# ZLL.net
KiCad netlist of a schematic drawn in EAGLE
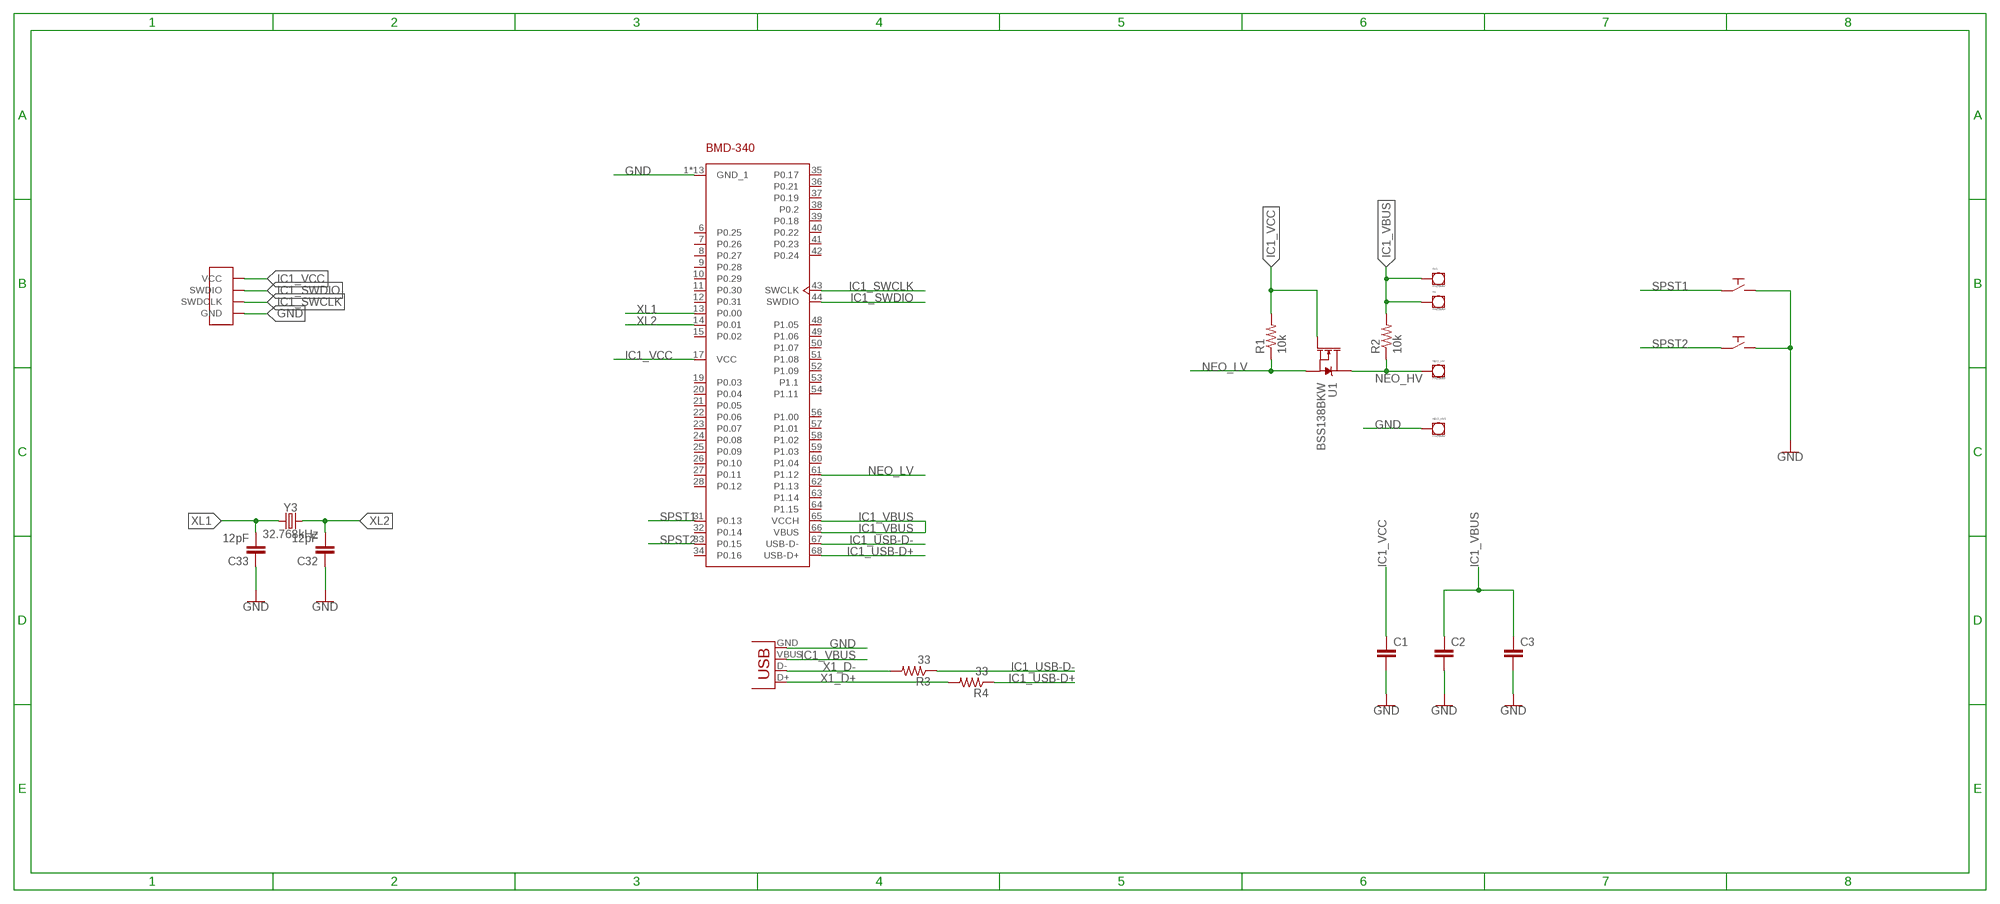
[diagram p0: schematic, sheet 1]

(export (version "E")
  (design (tool "Eeschema 10.0.6"))
  (components
    (comp (ref "5V")
      (value "PAD3MM")
      (footprint "eagle-import:PAD_3")
      (libsource (lib "eagle-import") (part "PAD3MM"))
    )
    (comp (ref "5V1")
      (value "PAD3MM")
      (footprint "eagle-import:PAD_3")
      (libsource (lib "eagle-import") (part "PAD3MM"))
    )
    (comp (ref "C1")
      (value "C-EUC0603")
      (footprint "eagle-import:C0603")
      (libsource (lib "eagle-import") (part "resistor_C-EUC0603"))
    )
    (comp (ref "C2")
      (value "C-EUC0805")
      (footprint "eagle-import:C0805")
      (libsource (lib "eagle-import") (part "resistor_C-EUC0805"))
    )
    (comp (ref "C3")
      (value "C-EUC0603")
      (footprint "eagle-import:C0603")
      (libsource (lib "eagle-import") (part "resistor_C-EUC0603"))
    )
    (comp (ref "C32")
      (value "12pF")
      (footprint "eagle-import:C0603")
      (libsource (lib "eagle-import") (part "C-EUC0603"))
    )
    (comp (ref "C33")
      (value "12pF")
      (footprint "eagle-import:C0603")
      (libsource (lib "eagle-import") (part "C-EUC0603"))
    )
    (comp (ref "IC1")
      (value "BMD-340-A-R")
      (footprint "eagle-import:BMD340AR")
      (fields (field (name "MOUSER_PART_NUMBER") "377-BMD-340-A-R"))
      (libsource (lib "eagle-import") (part "BMD-340-A-R"))
    )
    (comp (ref "NEO_HV")
      (value "PAD3MM")
      (footprint "eagle-import:PAD_3")
      (libsource (lib "eagle-import") (part "PAD3MM"))
    )
    (comp (ref "NEO_HV1")
      (value "PAD3MM")
      (footprint "eagle-import:PAD_3")
      (libsource (lib "eagle-import") (part "PAD3MM"))
    )
    (comp (ref "R1")
      (value "10k")
      (footprint "eagle-import:R0603")
      (libsource (lib "eagle-import") (part "R-US_R0603"))
    )
    (comp (ref "R2")
      (value "10k")
      (footprint "eagle-import:R0603")
      (libsource (lib "eagle-import") (part "R-US_R0603"))
    )
    (comp (ref "R3")
      (value "33")
      (footprint "eagle-import:R0603")
      (libsource (lib "eagle-import") (part "R-US_R0603"))
    )
    (comp (ref "R4")
      (value "33")
      (footprint "eagle-import:R0603")
      (libsource (lib "eagle-import") (part "R-US_R0603"))
    )
    (comp (ref "SPST1")
      (value "PTS526SK08")
      (footprint "eagle-import:PTS526SKG15SMTR2LFS")
      (libsource (lib "eagle-import") (part "PTS526SK08"))
    )
    (comp (ref "SPST2")
      (value "PTS526SK08")
      (footprint "eagle-import:PTS526SKG15SMTR2LFS")
      (libsource (lib "eagle-import") (part "PTS526SK08"))
    )
    (comp (ref "U$1")
      (value "PROG_SMD")
      (footprint "eagle-import:PROG_SMD")
      (libsource (lib "eagle-import") (part "PROG_SMD"))
    )
    (comp (ref "U1")
      (value "BSS138BKW")
      (footprint "eagle-import:SOT65P210X110-3N")
      (libsource (lib "eagle-import") (part "BSS138BKW"))
    )
    (comp (ref "X1")
      (value "USB-MICROB")
      (footprint "eagle-import:USB-MICROB")
      (libsource (lib "eagle-import") (part "USB-MICROB"))
    )
    (comp (ref "Y3")
      (value "32.768kHz")
      (footprint "eagle-import:CRYSTAL-SMD-3.2X1.5MM")
      (libsource (lib "eagle-import") (part "CRYSTAL-32.768KHZSMD-3.2X1.5"))
    )
  )
  (nets
    (net (code "1") (name "/IC1_USB-D+") (class "Default")
      (node (ref "IC1") (pin "68") (pinfunction "USB-D+_68") (pintype "bidirectional"))
      (node (ref "R4") (pin "1") (pinfunction "1_1") (pintype "passive"))
    )
    (net (code "2") (name "/IC1_USB-D-") (class "Default")
      (node (ref "IC1") (pin "67") (pinfunction "USB-D-_67") (pintype "bidirectional"))
      (node (ref "R3") (pin "1") (pinfunction "1_1") (pintype "passive"))
    )
    (net (code "3") (name "/NEO_HV") (class "Default")
      (node (ref "NEO_HV") (pin "P$1") (pinfunction "1_P$1") (pintype "passive"))
      (node (ref "R2") (pin "1") (pinfunction "1_1") (pintype "passive"))
      (node (ref "U1") (pin "3") (pinfunction "D_3") (pintype "bidirectional"))
    )
    (net (code "4") (name "/NEO_LV") (class "Default")
      (node (ref "IC1") (pin "61") (pinfunction "P1.12_61") (pintype "bidirectional"))
      (node (ref "R1") (pin "1") (pinfunction "1_1") (pintype "passive"))
      (node (ref "U1") (pin "2") (pinfunction "S_2") (pintype "bidirectional"))
    )
    (net (code "5") (name "/SPST1") (class "Default")
      (node (ref "IC1") (pin "31") (pinfunction "P0.13_31") (pintype "bidirectional"))
      (node (ref "SPST1") (pin "1") (pinfunction "P$1_1") (pintype "passive"))
      (node (ref "SPST1") (pin "2") (pinfunction "P$1_2") (pintype "passive"))
    )
    (net (code "6") (name "/SPST2") (class "Default")
      (node (ref "IC1") (pin "33") (pinfunction "P0.15_33") (pintype "bidirectional"))
      (node (ref "SPST2") (pin "1") (pinfunction "P$1_1") (pintype "passive"))
      (node (ref "SPST2") (pin "2") (pinfunction "P$1_2") (pintype "passive"))
    )
    (net (code "7") (name "/X1_D+") (class "Default")
      (node (ref "R4") (pin "2") (pinfunction "2_2") (pintype "passive"))
      (node (ref "X1") (pin "D+") (pinfunction "D+_D+") (pintype "bidirectional"))
    )
    (net (code "8") (name "/X1_D-") (class "Default")
      (node (ref "R3") (pin "2") (pinfunction "2_2") (pintype "passive"))
      (node (ref "X1") (pin "D-") (pinfunction "D-_D-") (pintype "bidirectional"))
    )
    (net (code "9") (name "GND") (class "Default")
      (node (ref "C1") (pin "2") (pinfunction "2_2") (pintype "passive"))
      (node (ref "C2") (pin "2") (pinfunction "2_2") (pintype "passive"))
      (node (ref "C3") (pin "2") (pinfunction "2_2") (pintype "passive"))
      (node (ref "C32") (pin "1") (pinfunction "1_1") (pintype "passive"))
      (node (ref "C33") (pin "1") (pinfunction "1_1") (pintype "passive"))
      (node (ref "IC1") (pin "1") (pinfunction "GND_1_1") (pintype "power_in"))
      (node (ref "IC1") (pin "16") (pinfunction "GND_1_16") (pintype "power_in"))
      (node (ref "IC1") (pin "18") (pinfunction "GND_1_18") (pintype "power_in"))
      (node (ref "IC1") (pin "2") (pinfunction "GND_1_2") (pintype "power_in"))
      (node (ref "IC1") (pin "29") (pinfunction "GND_1_29") (pintype "power_in"))
      (node (ref "IC1") (pin "3") (pinfunction "GND_1_3") (pintype "power_in"))
      (node (ref "IC1") (pin "30") (pinfunction "GND_1_30") (pintype "power_in"))
      (node (ref "IC1") (pin "4") (pinfunction "GND_1_4") (pintype "power_in"))
      (node (ref "IC1") (pin "45") (pinfunction "GND_1_45") (pintype "power_in"))
      (node (ref "IC1") (pin "46") (pinfunction "GND_1_46") (pintype "power_in"))
      (node (ref "IC1") (pin "47") (pinfunction "GND_1_47") (pintype "power_in"))
      (node (ref "IC1") (pin "5") (pinfunction "GND_1_5") (pintype "power_in"))
      (node (ref "IC1") (pin "55") (pinfunction "GND_1_55") (pintype "power_in"))
      (node (ref "NEO_HV1") (pin "P$1") (pinfunction "1_P$1") (pintype "passive"))
      (node (ref "SPST1") (pin "3") (pinfunction "P$2_3") (pintype "passive"))
      (node (ref "SPST1") (pin "4") (pinfunction "P$2_4") (pintype "passive"))
      (node (ref "SPST2") (pin "3") (pinfunction "P$2_3") (pintype "passive"))
      (node (ref "SPST2") (pin "4") (pinfunction "P$2_4") (pintype "passive"))
      (node (ref "U$1") (pin "GND") (pinfunction "GND_GND") (pintype "bidirectional"))
      (node (ref "X1") (pin "GND") (pinfunction "GND_GND") (pintype "bidirectional"))
    )
    (net (code "10") (name "IC1_SWCLK") (class "Default")
      (node (ref "IC1") (pin "43") (pinfunction "SWCLK_43") (pintype "bidirectional"))
      (node (ref "U$1") (pin "PIN1") (pinfunction "SWDCLK_PIN1") (pintype "bidirectional"))
    )
    (net (code "11") (name "IC1_SWDIO") (class "Default")
      (node (ref "IC1") (pin "44") (pinfunction "SWDIO_44") (pintype "bidirectional"))
      (node (ref "U$1") (pin "PIN2") (pinfunction "SWDIO_PIN2") (pintype "bidirectional"))
    )
    (net (code "12") (name "IC1_VBUS") (class "Default")
      (node (ref "5V") (pin "P$1") (pinfunction "1_P$1") (pintype "passive"))
      (node (ref "5V1") (pin "P$1") (pinfunction "1_P$1") (pintype "passive"))
      (node (ref "C2") (pin "1") (pinfunction "1_1") (pintype "passive"))
      (node (ref "C3") (pin "1") (pinfunction "1_1") (pintype "passive"))
      (node (ref "IC1") (pin "65") (pinfunction "VCCH_65") (pintype "input"))
      (node (ref "IC1") (pin "66") (pinfunction "VBUS_66") (pintype "bidirectional"))
      (node (ref "R2") (pin "2") (pinfunction "2_2") (pintype "passive"))
      (node (ref "X1") (pin "VBUS") (pinfunction "VBUS_VBUS") (pintype "bidirectional"))
    )
    (net (code "13") (name "IC1_VCC") (class "Default")
      (node (ref "C1") (pin "1") (pinfunction "1_1") (pintype "passive"))
      (node (ref "IC1") (pin "17") (pinfunction "VCC_17") (pintype "power_in"))
      (node (ref "R1") (pin "2") (pinfunction "2_2") (pintype "passive"))
      (node (ref "U$1") (pin "VCC") (pinfunction "VCC_VCC") (pintype "bidirectional"))
      (node (ref "U1") (pin "1") (pinfunction "G_1") (pintype "bidirectional"))
    )
    (net (code "14") (name "XL1") (class "Default")
      (node (ref "C33") (pin "2") (pinfunction "2_2") (pintype "passive"))
      (node (ref "IC1") (pin "13") (pinfunction "P0.00_13") (pintype "bidirectional"))
      (node (ref "Y3") (pin "P$1") (pinfunction "1_P$1") (pintype "passive"))
    )
    (net (code "15") (name "XL2") (class "Default")
      (node (ref "C32") (pin "2") (pinfunction "2_2") (pintype "passive"))
      (node (ref "IC1") (pin "14") (pinfunction "P0.01_14") (pintype "bidirectional"))
      (node (ref "Y3") (pin "P$2") (pinfunction "2_P$2") (pintype "passive"))
    )
    (net (code "16") (name "unconnected-(IC1-P0.02-Pad15)") (class "Default")
      (node (ref "IC1") (pin "15") (pinfunction "P0.02_15") (pintype "bidirectional"))
    )
    (net (code "17") (name "unconnected-(IC1-P0.2-Pad38)") (class "Default")
      (node (ref "IC1") (pin "38") (pinfunction "P0.2_38") (pintype "bidirectional"))
    )
    (net (code "18") (name "unconnected-(IC1-P0.03-Pad19)") (class "Default")
      (node (ref "IC1") (pin "19") (pinfunction "P0.03_19") (pintype "bidirectional"))
    )
    (net (code "19") (name "unconnected-(IC1-P0.04-Pad20)") (class "Default")
      (node (ref "IC1") (pin "20") (pinfunction "P0.04_20") (pintype "bidirectional"))
    )
    (net (code "20") (name "unconnected-(IC1-P0.05-Pad21)") (class "Default")
      (node (ref "IC1") (pin "21") (pinfunction "P0.05_21") (pintype "bidirectional"))
    )
    (net (code "21") (name "unconnected-(IC1-P0.06-Pad22)") (class "Default")
      (node (ref "IC1") (pin "22") (pinfunction "P0.06_22") (pintype "bidirectional"))
    )
    (net (code "22") (name "unconnected-(IC1-P0.07-Pad23)") (class "Default")
      (node (ref "IC1") (pin "23") (pinfunction "P0.07_23") (pintype "bidirectional"))
    )
    (net (code "23") (name "unconnected-(IC1-P0.08-Pad24)") (class "Default")
      (node (ref "IC1") (pin "24") (pinfunction "P0.08_24") (pintype "bidirectional"))
    )
    (net (code "24") (name "unconnected-(IC1-P0.09-Pad25)") (class "Default")
      (node (ref "IC1") (pin "25") (pinfunction "P0.09_25") (pintype "bidirectional"))
    )
    (net (code "25") (name "unconnected-(IC1-P0.10-Pad26)") (class "Default")
      (node (ref "IC1") (pin "26") (pinfunction "P0.10_26") (pintype "bidirectional"))
    )
    (net (code "26") (name "unconnected-(IC1-P0.11-Pad27)") (class "Default")
      (node (ref "IC1") (pin "27") (pinfunction "P0.11_27") (pintype "bidirectional"))
    )
    (net (code "27") (name "unconnected-(IC1-P0.12-Pad28)") (class "Default")
      (node (ref "IC1") (pin "28") (pinfunction "P0.12_28") (pintype "bidirectional"))
    )
    (net (code "28") (name "unconnected-(IC1-P0.14-Pad32)") (class "Default")
      (node (ref "IC1") (pin "32") (pinfunction "P0.14_32") (pintype "bidirectional"))
    )
    (net (code "29") (name "unconnected-(IC1-P0.16-Pad34)") (class "Default")
      (node (ref "IC1") (pin "34") (pinfunction "P0.16_34") (pintype "bidirectional"))
    )
    (net (code "30") (name "unconnected-(IC1-P0.17-Pad35)") (class "Default")
      (node (ref "IC1") (pin "35") (pinfunction "P0.17_35") (pintype "bidirectional"))
    )
    (net (code "31") (name "unconnected-(IC1-P0.18-Pad39)") (class "Default")
      (node (ref "IC1") (pin "39") (pinfunction "P0.18_39") (pintype "bidirectional"))
    )
    (net (code "32") (name "unconnected-(IC1-P0.19-Pad37)") (class "Default")
      (node (ref "IC1") (pin "37") (pinfunction "P0.19_37") (pintype "bidirectional"))
    )
    (net (code "33") (name "unconnected-(IC1-P0.21-Pad36)") (class "Default")
      (node (ref "IC1") (pin "36") (pinfunction "P0.21_36") (pintype "bidirectional"))
    )
    (net (code "34") (name "unconnected-(IC1-P0.22-Pad40)") (class "Default")
      (node (ref "IC1") (pin "40") (pinfunction "P0.22_40") (pintype "bidirectional"))
    )
    (net (code "35") (name "unconnected-(IC1-P0.23-Pad41)") (class "Default")
      (node (ref "IC1") (pin "41") (pinfunction "P0.23_41") (pintype "bidirectional"))
    )
    (net (code "36") (name "unconnected-(IC1-P0.24-Pad42)") (class "Default")
      (node (ref "IC1") (pin "42") (pinfunction "P0.24_42") (pintype "bidirectional"))
    )
    (net (code "37") (name "unconnected-(IC1-P0.25-Pad6)") (class "Default")
      (node (ref "IC1") (pin "6") (pinfunction "P0.25_6") (pintype "bidirectional"))
    )
    (net (code "38") (name "unconnected-(IC1-P0.26-Pad7)") (class "Default")
      (node (ref "IC1") (pin "7") (pinfunction "P0.26_7") (pintype "bidirectional"))
    )
    (net (code "39") (name "unconnected-(IC1-P0.27-Pad8)") (class "Default")
      (node (ref "IC1") (pin "8") (pinfunction "P0.27_8") (pintype "bidirectional"))
    )
    (net (code "40") (name "unconnected-(IC1-P0.28-Pad9)") (class "Default")
      (node (ref "IC1") (pin "9") (pinfunction "P0.28_9") (pintype "bidirectional"))
    )
    (net (code "41") (name "unconnected-(IC1-P0.29-Pad10)") (class "Default")
      (node (ref "IC1") (pin "10") (pinfunction "P0.29_10") (pintype "bidirectional"))
    )
    (net (code "42") (name "unconnected-(IC1-P0.30-Pad11)") (class "Default")
      (node (ref "IC1") (pin "11") (pinfunction "P0.30_11") (pintype "bidirectional"))
    )
    (net (code "43") (name "unconnected-(IC1-P0.31-Pad12)") (class "Default")
      (node (ref "IC1") (pin "12") (pinfunction "P0.31_12") (pintype "bidirectional"))
    )
    (net (code "44") (name "unconnected-(IC1-P1.00-Pad56)") (class "Default")
      (node (ref "IC1") (pin "56") (pinfunction "P1.00_56") (pintype "bidirectional"))
    )
    (net (code "45") (name "unconnected-(IC1-P1.1-Pad53)") (class "Default")
      (node (ref "IC1") (pin "53") (pinfunction "P1.1_53") (pintype "bidirectional"))
    )
    (net (code "46") (name "unconnected-(IC1-P1.01-Pad57)") (class "Default")
      (node (ref "IC1") (pin "57") (pinfunction "P1.01_57") (pintype "bidirectional"))
    )
    (net (code "47") (name "unconnected-(IC1-P1.02-Pad58)") (class "Default")
      (node (ref "IC1") (pin "58") (pinfunction "P1.02_58") (pintype "bidirectional"))
    )
    (net (code "48") (name "unconnected-(IC1-P1.03-Pad59)") (class "Default")
      (node (ref "IC1") (pin "59") (pinfunction "P1.03_59") (pintype "bidirectional"))
    )
    (net (code "49") (name "unconnected-(IC1-P1.04-Pad60)") (class "Default")
      (node (ref "IC1") (pin "60") (pinfunction "P1.04_60") (pintype "bidirectional"))
    )
    (net (code "50") (name "unconnected-(IC1-P1.05-Pad48)") (class "Default")
      (node (ref "IC1") (pin "48") (pinfunction "P1.05_48") (pintype "bidirectional"))
    )
    (net (code "51") (name "unconnected-(IC1-P1.06-Pad49)") (class "Default")
      (node (ref "IC1") (pin "49") (pinfunction "P1.06_49") (pintype "bidirectional"))
    )
    (net (code "52") (name "unconnected-(IC1-P1.07-Pad50)") (class "Default")
      (node (ref "IC1") (pin "50") (pinfunction "P1.07_50") (pintype "bidirectional"))
    )
    (net (code "53") (name "unconnected-(IC1-P1.08-Pad51)") (class "Default")
      (node (ref "IC1") (pin "51") (pinfunction "P1.08_51") (pintype "bidirectional"))
    )
    (net (code "54") (name "unconnected-(IC1-P1.09-Pad52)") (class "Default")
      (node (ref "IC1") (pin "52") (pinfunction "P1.09_52") (pintype "bidirectional"))
    )
    (net (code "55") (name "unconnected-(IC1-P1.11-Pad54)") (class "Default")
      (node (ref "IC1") (pin "54") (pinfunction "P1.11_54") (pintype "bidirectional"))
    )
    (net (code "56") (name "unconnected-(IC1-P1.13-Pad62)") (class "Default")
      (node (ref "IC1") (pin "62") (pinfunction "P1.13_62") (pintype "bidirectional"))
    )
    (net (code "57") (name "unconnected-(IC1-P1.14-Pad63)") (class "Default")
      (node (ref "IC1") (pin "63") (pinfunction "P1.14_63") (pintype "bidirectional"))
    )
    (net (code "58") (name "unconnected-(IC1-P1.15-Pad64)") (class "Default")
      (node (ref "IC1") (pin "64") (pinfunction "P1.15_64") (pintype "bidirectional"))
    )
  )
)
